# 1_Schematic.net
KiCad netlist of a schematic drawn in Altium Designer
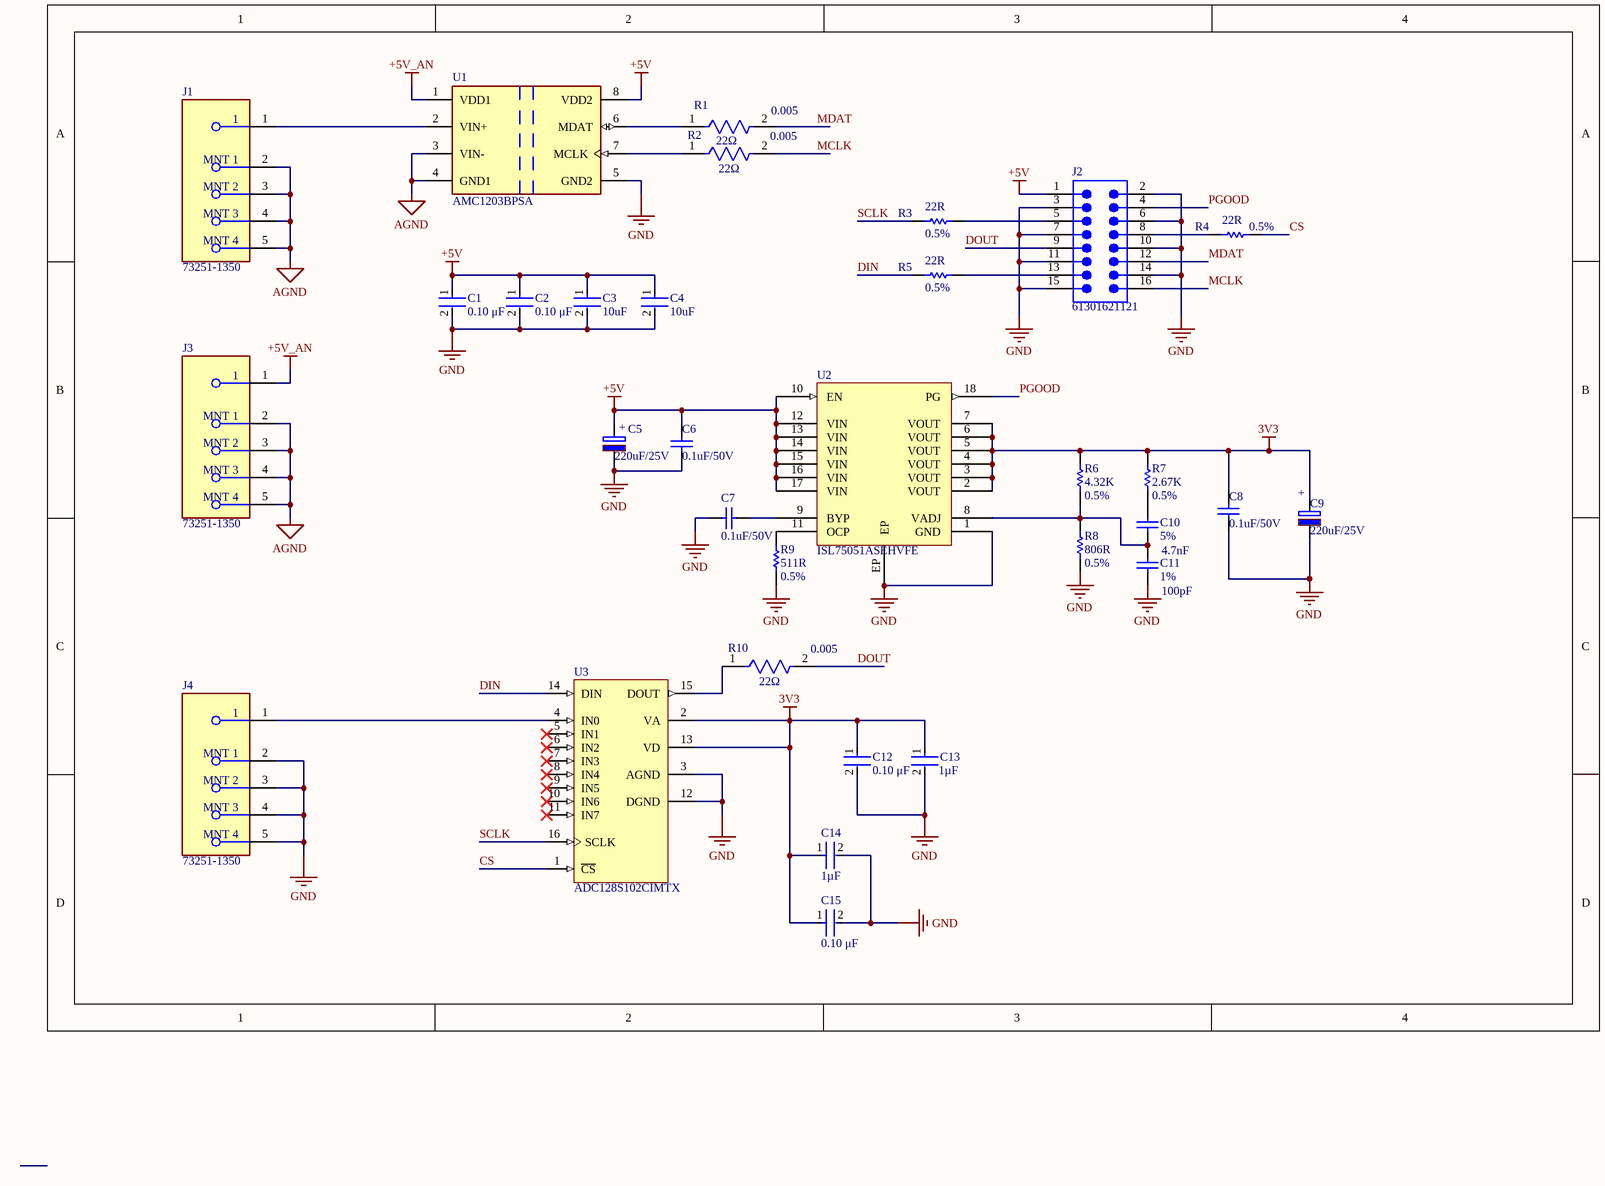
[diagram p0: 1_Schematic.SchDoc]

(export (version "E")
  (design (tool "Eeschema 10.0.6"))
  (components
    (comp (ref "C1")
      (value "C0603C104J5RACTU")
      (footprint "FP-C0603C-CF-MFG")
      (description "CAP CER 0.1UF 50V 5% X7R 0603")
      (fields
        (field (name "TOLERANCE") "0.05")
        (field (name "CAPACITANCE") "0.10 μF")
        (field (name "OCTOPART") "https://octopart.com/c0603c104j5ractu-kemet-10440638")
      )
      (libsource (lib "Altium Content Vault") (part "b4654b650e69147ec39a6b967a45e02"))
    )
    (comp (ref "C2")
      (value "C0603C104J5RACTU")
      (footprint "FP-C0603C-CF-MFG")
      (description "CAP CER 0.1UF 50V 5% X7R 0603")
      (fields
        (field (name "TOLERANCE") "0.05")
        (field (name "CAPACITANCE") "0.10 μF")
        (field (name "OCTOPART") "https://octopart.com/c0603c104j5ractu-kemet-10440638")
      )
      (libsource (lib "Altium Content Vault") (part "b4654b650e69147ec39a6b967a45e02"))
    )
    (comp (ref "C3")
      (value "10uF")
      (footprint "FP-GRM188-0_2-IPC_A")
      (description "Chip Multilayer Ceramic Capacitors for General Purpose, 0603, 10uF, X5R, 15%, 10%, 25V")
      (fields (field (name "Comment") "GRM188R61E106KA73D"))
      (libsource (lib "Altium Content Vault") (part "11868f565c42a9108669ba33697ecf6"))
    )
    (comp (ref "C4")
      (value "10uF")
      (footprint "FP-GRM188-0_2-IPC_A")
      (description "Chip Multilayer Ceramic Capacitors for General Purpose, 0603, 10uF, X5R, 15%, 10%, 25V")
      (fields (field (name "Comment") "GRM188R61E106KA73D"))
      (libsource (lib "Altium Content Vault") (part "11868f565c42a9108669ba33697ecf6"))
    )
    (comp (ref "C5")
      (value "220uF/25V")
      (footprint "CAP_AE830X1050N")
      (description "CAP ALUM 220UF 20% 25V SMD")
      (fields
        (field (name "MANUFACTURER PART NUMBER") "EMZA250ADA221MHA0G")
        (field (name "MANUFACTURER") "United Chemi-Con")
      )
      (libsource (lib "") (part "CAP ALUM 220UF 20% 25V SMD_1"))
    )
    (comp (ref "C6")
      (value "0.1uF/50V")
      (footprint "CAPC1608X90N")
      (description "CAP CER 0.1UF 50V X7R 0603")
      (fields
        (field (name "MANUFACTURER PART NUMBER") "CL10B104KB8NNNC")
        (field (name "MANUFACTURER") "Samsung Electro-Mechanics")
      )
      (libsource (lib "Motor Resolver") (part "CAP CER 0.1UF 50V X7R 0603"))
    )
    (comp (ref "C7")
      (value "0.1uF/50V")
      (footprint "CAPC1608X90N")
      (description "CAP CER 0.1UF 50V X7R 0603")
      (fields
        (field (name "MANUFACTURER PART NUMBER") "CL10B104KB8NNNC")
        (field (name "MANUFACTURER") "Samsung Electro-Mechanics")
      )
      (libsource (lib "Motor Resolver") (part "CAP CER 0.1UF 50V X7R 0603"))
    )
    (comp (ref "C8")
      (value "0.1uF/50V")
      (footprint "CAPC1608X90N")
      (description "CAP CER 0.1UF 50V X7R 0603")
      (fields
        (field (name "MANUFACTURER PART NUMBER") "CL10B104KB8NNNC")
        (field (name "MANUFACTURER") "Samsung Electro-Mechanics")
      )
      (libsource (lib "Motor Resolver") (part "CAP CER 0.1UF 50V X7R 0603"))
    )
    (comp (ref "C9")
      (value "220uF/25V")
      (footprint "CAP_AE830X1050N")
      (description "CAP ALUM 220UF 20% 25V SMD")
      (fields
        (field (name "MANUFACTURER PART NUMBER") "EMZA250ADA221MHA0G")
        (field (name "MANUFACTURER") "United Chemi-Con")
      )
      (libsource (lib "Motor Resolver") (part "CAP ALUM 220UF 20% 25V SMD"))
    )
    (comp (ref "C10")
      (value "4.7nF")
      (footprint "CAPC1608X90N")
      (description "CAP CER 4700PF 50V C0G 0603")
      (fields
        (field (name "MANUFACTURER PART NUMBER") "CGA3E2C0G1H472J080AA")
        (field (name "MANUFACTURER") "TDK Corporation")
        (field (name "TOLERANCE") "5%")
      )
      (libsource (lib "Motor Resolver") (part "CAP CER 4700PF 50V C0G 0603"))
    )
    (comp (ref "C11")
      (value "100pF")
      (footprint "CAPC1608X90N")
      (description "CAP CER 100PF 50V C0G/NP0 0603")
      (fields
        (field (name "MANUFACTURER PART NUMBER") "06035A101FAT2A")
        (field (name "MANUFACTURER") "KYOCERA AVX")
        (field (name "TOLERANCE") "1%")
      )
      (libsource (lib "Motor Resolver") (part "CAP CER 100PF 50V C0G/NP0 0603"))
    )
    (comp (ref "C12")
      (value "C0603C104J5RACTU")
      (footprint "FP-C0603C-CF-MFG")
      (description "CAP CER 0.1UF 50V 5% X7R 0603")
      (fields
        (field (name "TOLERANCE") "0.05")
        (field (name "CAPACITANCE") "0.10 μF")
        (field (name "OCTOPART") "https://octopart.com/c0603c104j5ractu-kemet-10440638")
      )
      (libsource (lib "Altium Content Vault") (part "b4654b650e69147ec39a6b967a45e02"))
    )
    (comp (ref "C13")
      (value "GCM188R71E105KA64D")
      (footprint "FP-GCM188-0_1-MFG")
      (fields
        (field (name "TOLERANCE") "10%")
        (field (name "CAPACITANCE") "1µF")
        (field (name "VOLTAGE") "25V")
      )
      (libsource (lib "Altium Content Vault") (part "02cd4be3c70576c341d710602a673aa"))
    )
    (comp (ref "C14")
      (value "GCM188R71E105KA64D")
      (footprint "FP-GCM188-0_1-MFG")
      (fields
        (field (name "TOLERANCE") "10%")
        (field (name "CAPACITANCE") "1µF")
        (field (name "VOLTAGE") "25V")
      )
      (libsource (lib "Altium Content Vault") (part "02cd4be3c70576c341d710602a673aa"))
    )
    (comp (ref "C15")
      (value "C0603C104J5RACTU")
      (footprint "FP-C0603C-CF-MFG")
      (description "CAP CER 0.1UF 50V 5% X7R 0603")
      (fields
        (field (name "TOLERANCE") "0.05")
        (field (name "CAPACITANCE") "0.10 μF")
        (field (name "OCTOPART") "https://octopart.com/c0603c104j5ractu-kemet-10440638")
      )
      (libsource (lib "Altium Content Vault") (part "b4654b650e69147ec39a6b967a45e02"))
    )
    (comp (ref "J1")
      (value "73251-1350")
      (footprint "FP-73251-1350-MFG")
      (description "CONN SMA JACK STR 50 OHM SMD")
      (fields
        (field (name "OCTOPART") "https://octopart.com/73251-1350-molex-5414390")
        (field (name "MANUFACTURER") "Molex")
      )
      (libsource (lib "Altium Content Vault") (part "474d33b8a96b1ade9ed6dd87a2b06d4"))
    )
    (comp (ref "J2")
      (value "61301621121")
      (footprint "61301621121")
      (libsource (lib "Altium Content Vault") (part "Header_Male_2R_16P"))
    )
    (comp (ref "J3")
      (value "73251-1350")
      (footprint "FP-73251-1350-MFG")
      (description "CONN SMA JACK STR 50 OHM SMD")
      (fields
        (field (name "OCTOPART") "https://octopart.com/73251-1350-molex-5414390")
        (field (name "MANUFACTURER") "Molex")
      )
      (libsource (lib "Altium Content Vault") (part "474d33b8a96b1ade9ed6dd87a2b06d4"))
    )
    (comp (ref "J4")
      (value "73251-1350")
      (footprint "FP-73251-1350-MFG")
      (description "CONN SMA JACK STR 50 OHM SMD")
      (fields
        (field (name "OCTOPART") "https://octopart.com/73251-1350-molex-5414390")
        (field (name "MANUFACTURER") "Molex")
      )
      (libsource (lib "Altium Content Vault") (part "474d33b8a96b1ade9ed6dd87a2b06d4"))
    )
    (comp (ref "R1")
      (value "22Ω")
      (footprint "FP-RT0603-MFG")
      (description "RES SMD 22 OHM 0.5% 1/10W 0603")
      (fields
        (field (name "TOLERANCE") "0.005")
        (field (name "MANUFACTURER PART NUMBER") "RT0603DRD0722RL")
        (field (name "MANUFACTURER") "Yageo")
      )
      (libsource (lib "Altium Content Vault") (part "1029c3af85768c4190bb7ad29bc67b5"))
    )
    (comp (ref "R2")
      (value "22Ω")
      (footprint "FP-RT0603-MFG")
      (description "RES SMD 22 OHM 0.5% 1/10W 0603")
      (fields
        (field (name "TOLERANCE") "0.005")
        (field (name "MANUFACTURER PART NUMBER") "RT0603DRD0722RL")
        (field (name "MANUFACTURER") "Yageo")
      )
      (libsource (lib "Altium Content Vault") (part "1029c3af85768c4190bb7ad29bc67b5"))
    )
    (comp (ref "R3")
      (value "22R")
      (footprint "RESC1608X55N")
      (description "RES SMD 22 OHM 0.5% 1/10W 0603")
      (fields
        (field (name "MANUFACTURER") "Yageo")
        (field (name "MANUFACTURER PART NUMBER") "RT0603DRD0722RL")
        (field (name "TOLERANCE") "0.5%")
      )
      (libsource (lib "Motor Resolver") (part "RES SMD 22 OHM 0.5% 1/10W 0603"))
    )
    (comp (ref "R4")
      (value "22R")
      (footprint "RESC1608X55N")
      (description "RES SMD 22 OHM 0.5% 1/10W 0603")
      (fields
        (field (name "MANUFACTURER") "Yageo")
        (field (name "MANUFACTURER PART NUMBER") "RT0603DRD0722RL")
        (field (name "TOLERANCE") "0.5%")
      )
      (libsource (lib "Motor Resolver") (part "RES SMD 22 OHM 0.5% 1/10W 0603"))
    )
    (comp (ref "R5")
      (value "22R")
      (footprint "RESC1608X55N")
      (description "RES SMD 22 OHM 0.5% 1/10W 0603")
      (fields
        (field (name "MANUFACTURER") "Yageo")
        (field (name "MANUFACTURER PART NUMBER") "RT0603DRD0722RL")
        (field (name "TOLERANCE") "0.5%")
      )
      (libsource (lib "Motor Resolver") (part "RES SMD 22 OHM 0.5% 1/10W 0603"))
    )
    (comp (ref "R6")
      (value "4.32K")
      (footprint "RESC1608X55N")
      (description "RES SMD 4.32K OHM 0.5% 1/5W 0603")
      (fields
        (field (name "MANUFACTURER") "Panasonic Electronic Components")
        (field (name "MANUFACTURER PART NUMBER") "ERJ-PB3D4321V")
        (field (name "TOLERANCE") "0.5%")
      )
      (libsource (lib "Motor Resolver") (part "RES SMD 4.32K OHM 0.5% 1/5W 0603"))
    )
    (comp (ref "R7")
      (value "2.67K")
      (footprint "RESC1608X55N")
      (description "RES SMD 2.67KOHM 0.5% 1/10W 0603")
      (fields
        (field (name "MANUFACTURER") "Yageo")
        (field (name "MANUFACTURER PART NUMBER") "RT0603DRD072K67L")
        (field (name "TOLERANCE") "0.5%")
      )
      (libsource (lib "Motor Resolver") (part "RES SMD 2.67KOHM 0.5% 1/10W 0603"))
    )
    (comp (ref "R8")
      (value "806R")
      (footprint "RESC1608X55N")
      (description "RES SMD 806 OHM 0.5% 1/10W 0603")
      (fields
        (field (name "MANUFACTURER") "Yageo")
        (field (name "MANUFACTURER PART NUMBER") "RT0603DRD0762KL")
        (field (name "TOLERANCE") "0.5%")
      )
      (libsource (lib "Motor Resolver") (part "RES SMD 806 OHM 0.5% 1/10W 0603"))
    )
    (comp (ref "R9")
      (value "511R")
      (footprint "RESC1608X55N")
      (description "RES SMD 511 OHM 1% 1/10W 0603")
      (fields
        (field (name "MANUFACTURER") "Panasonic Electronic Components")
        (field (name "MANUFACTURER PART NUMBER") "ERJ-3EKF5110V")
        (field (name "TOLERANCE") "0.5%")
      )
      (libsource (lib "Motor Resolver") (part "RES SMD 511 OHM 1% 1/10W 0603"))
    )
    (comp (ref "R10")
      (value "22Ω")
      (footprint "FP-RT0603-MFG")
      (description "RES SMD 22 OHM 0.5% 1/10W 0603")
      (fields
        (field (name "TOLERANCE") "0.005")
        (field (name "MANUFACTURER PART NUMBER") "RT0603DRD0722RL")
        (field (name "MANUFACTURER") "Yageo")
      )
      (libsource (lib "Altium Content Vault") (part "1029c3af85768c4190bb7ad29bc67b5"))
    )
    (comp (ref "U1")
      (value "AMC1203BPSA")
      (footprint "FP-PSA0008A-IPC_C")
      (description "IC ADC 16BIT SIGMA-DELTA 8SOP")
      (libsource (lib "Altium Content Vault") (part "402472702e68974f8122a6dcee3cdea"))
    )
    (comp (ref "U2")
      (value "ISL75051ASEHVFE")
      (footprint "CFP102P1520X310-18AN")
      (description "Voltage regulator, linear, variable, 3 A, CFP-18 exposed pad, class V")
      (fields
        (field (name "MANUFACTURER") "Renesas / Intersil")
        (field (name "EM PART NUMBER") "ISL75051ASEHFE/PROTO")
        (field (name "AVAILABLE PREVIEW IMAGES") "2D")
        (field (name "SOURCE") "IsolatedADCs.SCHLIB")
      )
      (libsource (lib "Industrial University of Ho Chi Minh City") (part "ISL75051ASEHVFE"))
    )
    (comp (ref "U3")
      (value "ADC128S102CIMTX")
      (footprint "MTC16_N")
      (description "8-Channel, 500 kSPS to 1 MSPS, 12-Bit A/D Converter, 16-pin TSSOP")
      (fields (field (name "MANUFACTURER") "National Semiconductor"))
      (libsource (lib "Altium Content Vault") (part "CON-ADC-ADC108S052CIMT"))
    )
  )
  (nets
    (net (code "1") (name "+5V") (class "Default")
      (node (ref "C1") (pin "1") (pinfunction "1_1") (pintype "passive"))
      (node (ref "C2") (pin "1") (pinfunction "1_1") (pintype "passive"))
      (node (ref "C3") (pin "1") (pinfunction "1_1") (pintype "passive"))
      (node (ref "C4") (pin "1") (pinfunction "1_1") (pintype "passive"))
      (node (ref "C5") (pin "1") (pinfunction "1_1") (pintype "passive"))
      (node (ref "C6") (pin "1") (pinfunction "1_1") (pintype "passive"))
      (node (ref "J2") (pin "1") (pinfunction "1_1") (pintype "passive"))
      (node (ref "U1") (pin "8") (pinfunction "VDD2_8") (pintype "power_in"))
      (node (ref "U2") (pin "10") (pinfunction "EN_10") (pintype "input"))
      (node (ref "U2") (pin "12") (pinfunction "VIN_12") (pintype "power_in"))
      (node (ref "U2") (pin "13") (pinfunction "VIN_13") (pintype "power_in"))
      (node (ref "U2") (pin "14") (pinfunction "VIN_14") (pintype "power_in"))
      (node (ref "U2") (pin "15") (pinfunction "VIN_15") (pintype "power_in"))
      (node (ref "U2") (pin "16") (pinfunction "VIN_16") (pintype "power_in"))
      (node (ref "U2") (pin "17") (pinfunction "VIN_17") (pintype "power_in"))
    )
    (net (code "2") (name "+5V_AN") (class "Default")
      (node (ref "J3") (pin "1") (pinfunction "1_1") (pintype "passive"))
      (node (ref "U1") (pin "1") (pinfunction "VDD1_1") (pintype "power_in"))
    )
    (net (code "3") (name "/CS") (class "Default")
      (node (ref "R4") (pin "2") (pinfunction "2_2") (pintype "passive"))
      (node (ref "U3") (pin "1") (pinfunction "~{CS}_1") (pintype "input"))
    )
    (net (code "4") (name "/DIN") (class "Default")
      (node (ref "R5") (pin "1") (pinfunction "1_1") (pintype "passive"))
      (node (ref "U3") (pin "14") (pinfunction "DIN_14") (pintype "input"))
    )
    (net (code "5") (name "/DOUT") (class "Default")
      (node (ref "J2") (pin "9") (pinfunction "9_9") (pintype "passive"))
      (node (ref "R10") (pin "2") (pinfunction "2_2") (pintype "passive"))
    )
    (net (code "6") (name "/MCLK") (class "Default")
      (node (ref "J2") (pin "16") (pinfunction "16_16") (pintype "passive"))
      (node (ref "R2") (pin "2") (pinfunction "2_2") (pintype "passive"))
    )
    (net (code "7") (name "/MDAT") (class "Default")
      (node (ref "J2") (pin "12") (pinfunction "12_12") (pintype "passive"))
      (node (ref "R1") (pin "2") (pinfunction "2_2") (pintype "passive"))
    )
    (net (code "8") (name "/PGOOD") (class "Default")
      (node (ref "J2") (pin "4") (pinfunction "4_4") (pintype "passive"))
      (node (ref "U2") (pin "18") (pinfunction "PG_18") (pintype "output"))
    )
    (net (code "9") (name "/SCLK") (class "Default")
      (node (ref "R3") (pin "1") (pinfunction "1_1") (pintype "passive"))
      (node (ref "U3") (pin "16") (pinfunction "SCLK_16") (pintype "input"))
    )
    (net (code "10") (name "3V3") (class "Default")
      (node (ref "C12") (pin "1") (pinfunction "1_1") (pintype "passive"))
      (node (ref "C13") (pin "1") (pinfunction "1_1") (pintype "passive"))
      (node (ref "C14") (pin "1") (pinfunction "1_1") (pintype "passive"))
      (node (ref "C15") (pin "1") (pinfunction "1_1") (pintype "passive"))
      (node (ref "C8") (pin "1") (pinfunction "1_1") (pintype "passive"))
      (node (ref "C9") (pin "1") (pinfunction "1_1") (pintype "passive"))
      (node (ref "R6") (pin "2") (pinfunction "2_2") (pintype "passive"))
      (node (ref "R7") (pin "2") (pinfunction "2_2") (pintype "passive"))
      (node (ref "U2") (pin "2") (pinfunction "VOUT_2") (pintype "power_in"))
      (node (ref "U2") (pin "3") (pinfunction "VOUT_3") (pintype "power_in"))
      (node (ref "U2") (pin "4") (pinfunction "VOUT_4") (pintype "power_in"))
      (node (ref "U2") (pin "5") (pinfunction "VOUT_5") (pintype "power_in"))
      (node (ref "U2") (pin "6") (pinfunction "VOUT_6") (pintype "power_in"))
      (node (ref "U2") (pin "7") (pinfunction "VOUT_7") (pintype "power_in"))
      (node (ref "U3") (pin "13") (pinfunction "VD_13") (pintype "power_in"))
      (node (ref "U3") (pin "2") (pinfunction "VA_2") (pintype "power_in"))
    )
    (net (code "11") (name "AGND") (class "Default")
      (node (ref "J1") (pin "2") (pinfunction "MNT_1_2") (pintype "passive"))
      (node (ref "J1") (pin "3") (pinfunction "MNT_2_3") (pintype "passive"))
      (node (ref "J1") (pin "4") (pinfunction "MNT_3_4") (pintype "passive"))
      (node (ref "J1") (pin "5") (pinfunction "MNT_4_5") (pintype "passive"))
      (node (ref "J3") (pin "2") (pinfunction "MNT_1_2") (pintype "passive"))
      (node (ref "J3") (pin "3") (pinfunction "MNT_2_3") (pintype "passive"))
      (node (ref "J3") (pin "4") (pinfunction "MNT_3_4") (pintype "passive"))
      (node (ref "J3") (pin "5") (pinfunction "MNT_4_5") (pintype "passive"))
      (node (ref "U1") (pin "3") (pinfunction "VIN-_3") (pintype "power_in"))
      (node (ref "U1") (pin "4") (pinfunction "GND1_4") (pintype "power_in"))
    )
    (net (code "12") (name "GND") (class "Default")
      (node (ref "C1") (pin "2") (pinfunction "2_2") (pintype "passive"))
      (node (ref "C11") (pin "2") (pinfunction "2_2") (pintype "passive"))
      (node (ref "C12") (pin "2") (pinfunction "2_2") (pintype "passive"))
      (node (ref "C13") (pin "2") (pinfunction "2_2") (pintype "passive"))
      (node (ref "C14") (pin "2") (pinfunction "2_2") (pintype "passive"))
      (node (ref "C15") (pin "2") (pinfunction "2_2") (pintype "passive"))
      (node (ref "C2") (pin "2") (pinfunction "2_2") (pintype "passive"))
      (node (ref "C3") (pin "2") (pinfunction "2_2") (pintype "passive"))
      (node (ref "C4") (pin "2") (pinfunction "2_2") (pintype "passive"))
      (node (ref "C5") (pin "2") (pinfunction "2_2") (pintype "passive"))
      (node (ref "C6") (pin "2") (pinfunction "2_2") (pintype "passive"))
      (node (ref "C7") (pin "2") (pinfunction "2_2") (pintype "passive"))
      (node (ref "C8") (pin "2") (pinfunction "2_2") (pintype "passive"))
      (node (ref "C9") (pin "2") (pinfunction "2_2") (pintype "passive"))
      (node (ref "J2") (pin "10") (pinfunction "10_10") (pintype "passive"))
      (node (ref "J2") (pin "11") (pinfunction "11_11") (pintype "passive"))
      (node (ref "J2") (pin "14") (pinfunction "14_14") (pintype "passive"))
      (node (ref "J2") (pin "15") (pinfunction "15_15") (pintype "passive"))
      (node (ref "J2") (pin "2") (pinfunction "2_2") (pintype "passive"))
      (node (ref "J2") (pin "3") (pinfunction "3_3") (pintype "passive"))
      (node (ref "J2") (pin "6") (pinfunction "6_6") (pintype "passive"))
      (node (ref "J2") (pin "7") (pinfunction "7_7") (pintype "passive"))
      (node (ref "J4") (pin "2") (pinfunction "MNT_1_2") (pintype "passive"))
      (node (ref "J4") (pin "3") (pinfunction "MNT_2_3") (pintype "passive"))
      (node (ref "J4") (pin "4") (pinfunction "MNT_3_4") (pintype "passive"))
      (node (ref "J4") (pin "5") (pinfunction "MNT_4_5") (pintype "passive"))
      (node (ref "R8") (pin "1") (pinfunction "1_1") (pintype "passive"))
      (node (ref "R9") (pin "1") (pinfunction "1_1") (pintype "passive"))
      (node (ref "U1") (pin "5") (pinfunction "GND2_5") (pintype "power_in"))
      (node (ref "U2") (pin "1") (pinfunction "GND_1") (pintype "power_in"))
      (node (ref "U2") (pin "EP") (pinfunction "EP_EP") (pintype "passive"))
      (node (ref "U3") (pin "12") (pinfunction "DGND_12") (pintype "power_in"))
      (node (ref "U3") (pin "3") (pinfunction "AGND_3") (pintype "power_in"))
    )
    (net (code "13") (name "Net-(C10-Pad1)") (class "Default")
      (node (ref "C10") (pin "1") (pinfunction "1_1") (pintype "passive"))
      (node (ref "R7") (pin "1") (pinfunction "1_1") (pintype "passive"))
    )
    (net (code "14") (name "Net-(J2-Pad5)") (class "Default")
      (node (ref "J2") (pin "5") (pinfunction "5_5") (pintype "passive"))
      (node (ref "R3") (pin "2") (pinfunction "2_2") (pintype "passive"))
    )
    (net (code "15") (name "Net-(J2-Pad8)") (class "Default")
      (node (ref "J2") (pin "8") (pinfunction "8_8") (pintype "passive"))
      (node (ref "R4") (pin "1") (pinfunction "1_1") (pintype "passive"))
    )
    (net (code "16") (name "Net-(J2-Pad13)") (class "Default")
      (node (ref "J2") (pin "13") (pinfunction "13_13") (pintype "passive"))
      (node (ref "R5") (pin "2") (pinfunction "2_2") (pintype "passive"))
    )
    (net (code "17") (name "Net-(U1-MCLK)") (class "Default")
      (node (ref "R2") (pin "1") (pinfunction "1_1") (pintype "passive"))
      (node (ref "U1") (pin "7") (pinfunction "MCLK_7") (pintype "input"))
    )
    (net (code "18") (name "Net-(U1-MDAT)") (class "Default")
      (node (ref "R1") (pin "1") (pinfunction "1_1") (pintype "passive"))
      (node (ref "U1") (pin "6") (pinfunction "MDAT_6") (pintype "bidirectional"))
    )
    (net (code "19") (name "Net-(U1-VIN+)") (class "Default")
      (node (ref "J1") (pin "1") (pinfunction "1_1") (pintype "passive"))
      (node (ref "U1") (pin "2") (pinfunction "VIN+_2") (pintype "power_in"))
    )
    (net (code "20") (name "Net-(U2-BYP)") (class "Default")
      (node (ref "C7") (pin "1") (pinfunction "1_1") (pintype "passive"))
      (node (ref "U2") (pin "9") (pinfunction "BYP_9") (pintype "passive"))
    )
    (net (code "21") (name "Net-(U2-OCP)") (class "Default")
      (node (ref "R9") (pin "2") (pinfunction "2_2") (pintype "passive"))
      (node (ref "U2") (pin "11") (pinfunction "OCP_11") (pintype "passive"))
    )
    (net (code "22") (name "Net-(U2-VADJ)") (class "Default")
      (node (ref "C10") (pin "2") (pinfunction "2_2") (pintype "passive"))
      (node (ref "C11") (pin "1") (pinfunction "1_1") (pintype "passive"))
      (node (ref "R6") (pin "1") (pinfunction "1_1") (pintype "passive"))
      (node (ref "R8") (pin "2") (pinfunction "2_2") (pintype "passive"))
      (node (ref "U2") (pin "8") (pinfunction "VADJ_8") (pintype "passive"))
    )
    (net (code "23") (name "Net-(U3-DOUT)") (class "Default")
      (node (ref "R10") (pin "1") (pinfunction "1_1") (pintype "passive"))
      (node (ref "U3") (pin "15") (pinfunction "DOUT_15") (pintype "output"))
    )
    (net (code "24") (name "Net-(U3-IN0)") (class "Default")
      (node (ref "J4") (pin "1") (pinfunction "1_1") (pintype "passive"))
      (node (ref "U3") (pin "4") (pinfunction "IN0_4") (pintype "input"))
    )
    (net (code "25") (name "unconnected-(U3-IN1-Pad5)") (class "Default")
      (node (ref "U3") (pin "5") (pinfunction "IN1_5") (pintype "input+no_connect"))
    )
    (net (code "26") (name "unconnected-(U3-IN2-Pad6)") (class "Default")
      (node (ref "U3") (pin "6") (pinfunction "IN2_6") (pintype "input+no_connect"))
    )
    (net (code "27") (name "unconnected-(U3-IN3-Pad7)") (class "Default")
      (node (ref "U3") (pin "7") (pinfunction "IN3_7") (pintype "input+no_connect"))
    )
    (net (code "28") (name "unconnected-(U3-IN4-Pad8)") (class "Default")
      (node (ref "U3") (pin "8") (pinfunction "IN4_8") (pintype "input+no_connect"))
    )
    (net (code "29") (name "unconnected-(U3-IN5-Pad9)") (class "Default")
      (node (ref "U3") (pin "9") (pinfunction "IN5_9") (pintype "input+no_connect"))
    )
    (net (code "30") (name "unconnected-(U3-IN6-Pad10)") (class "Default")
      (node (ref "U3") (pin "10") (pinfunction "IN6_10") (pintype "input+no_connect"))
    )
    (net (code "31") (name "unconnected-(U3-IN7-Pad11)") (class "Default")
      (node (ref "U3") (pin "11") (pinfunction "IN7_11") (pintype "input+no_connect"))
    )
  )
)
